# LCL_12V_prec.net
KiCad netlist of a schematic drawn in Altium Designer
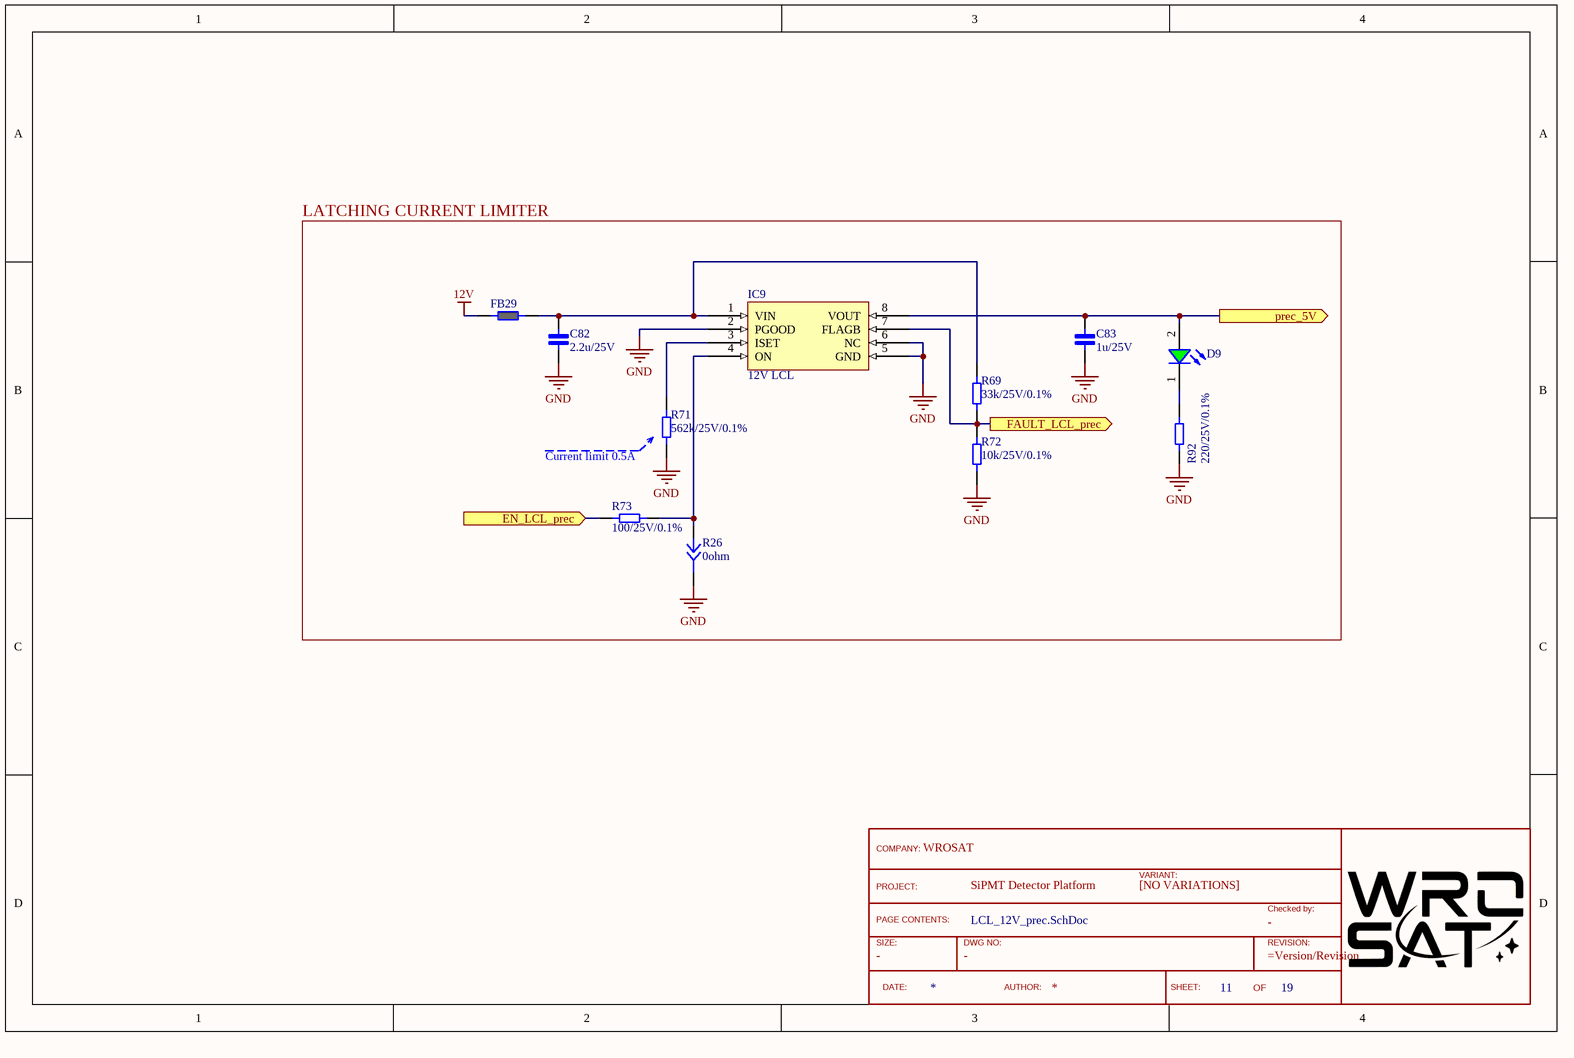
[diagram p0: LCL_12V_prec.SchDoc]

(export (version "E")
  (design (tool "Eeschema 10.0.6"))
  (components
    (comp (ref "C82")
      (value "2.2u/25V")
      (footprint "CAP_0603")
      (description "Ceramic Capacitor 2.2uF / 0603 / 25V / ±5%, Wurth Elektronik MLCC")
      (libsource (lib "Cubesat_lib") (part "Cap_0603_2.2u_25v"))
    )
    (comp (ref "C83")
      (value "1u/25V")
      (footprint "CAP_0603")
      (description "Ceramic Capacitor 1uF / 0603 / 25V / ±5%, Wurth Elektronik MLCC")
      (libsource (lib "Cubesat_lib") (part "Cap_0603_1u_25v"))
    )
    (comp (ref "D9")
      (value "Green, 3.2V")
      (footprint "WL-SMCW_0603_H=0.7mm")
      (description "WL-SMCW SMT Mono-color Chip LED Waterclear, size 0603, Green, 3.2V, 140deg")
      (fields (field (name "PART NUMBER") "150060GS75000") (field (name "PUBLISHER") "Wurth Elektronik"))
      (libsource (lib "LEDS") (part "150060GS75000"))
    )
    (comp (ref "FB29")
      (value "Ferrite_bead_0603")
      (footprint "Ferrite_0603")
      (description "Ferrite bead")
      (libsource (lib "Cubesat_lib") (part "Ferrite_bead_0603"))
    )
    (comp (ref "IC9")
      (value "12V LCL")
      (footprint "SO8")
      (description "FPF270xMX")
      (libsource (lib "Cubesat_lib") (part "FPF2700"))
    )
    (comp (ref "R26")
      (value "0ohm")
      (footprint "Jumper 2")
      (libsource (lib "Cubesat_lib") (part "Mini jumper"))
    )
    (comp (ref "R69")
      (value "33k/25V/0.1%")
      (footprint "RES_0402")
      (description "Vishay, thin film resistor 33k/25V/0.1%")
      (libsource (lib "Cubesat_lib") (part "Res_0402_33k"))
    )
    (comp (ref "R71")
      (value "562k/25V/0.1%")
      (footprint "RES_0402")
      (description "Vishay, thin film resistor 562k/25V/0.1%")
      (libsource (lib "Cubesat_lib") (part "Res_0402_562k"))
    )
    (comp (ref "R72")
      (value "10k/25V/0.1%")
      (footprint "RES_0402")
      (description "Vishay, thin film resistor 10k/25V/0.1%")
      (libsource (lib "Cubesat_lib") (part "Res_0402_10k"))
    )
    (comp (ref "R73")
      (value "100/25V/0.1%")
      (footprint "RES_0402")
      (description "Vishay, thin film resistor 100/25V/0.1%")
      (libsource (lib "Cubesat_lib") (part "Res_0402_100"))
    )
    (comp (ref "R92")
      (value "220/25V/0.1%")
      (footprint "RES_0402")
      (description "Vishay, thin film resistor 1/25V/0.1%")
      (libsource (lib "Cubesat_lib") (part "Res_0402_1"))
    )
  )
  (nets
    (net (code "1") (name "/EN_LCL_prec") (class "Default")
      (node (ref "R73") (pin "1") (pinfunction "1_1") (pintype "passive"))
    )
    (net (code "2") (name "/FAULT_LCL_prec") (class "Default")
      (node (ref "IC9") (pin "7") (pinfunction "FLAGB_7") (pintype "input"))
      (node (ref "R69") (pin "1") (pinfunction "1_1") (pintype "passive"))
      (node (ref "R72") (pin "2") (pinfunction "2_2") (pintype "passive"))
    )
    (net (code "3") (name "/prec_5V") (class "Default")
      (node (ref "C83") (pin "2") (pinfunction "2_2") (pintype "passive"))
      (node (ref "D9") (pin "2") (pinfunction "A_2") (pintype "passive"))
      (node (ref "IC9") (pin "8") (pinfunction "VOUT_8") (pintype "input"))
    )
    (net (code "4") (name "12V") (class "Default")
      (node (ref "FB29") (pin "1") (pinfunction "1_1") (pintype "passive"))
    )
    (net (code "5") (name "GND") (class "Default")
      (node (ref "C82") (pin "1") (pinfunction "1_1") (pintype "passive"))
      (node (ref "C83") (pin "1") (pinfunction "1_1") (pintype "passive"))
      (node (ref "IC9") (pin "2") (pinfunction "PGOOD_2") (pintype "input"))
      (node (ref "IC9") (pin "5") (pinfunction "GND_5") (pintype "input"))
      (node (ref "IC9") (pin "6") (pinfunction "NC_6") (pintype "input"))
      (node (ref "R26") (pin "2") (pinfunction "2_2") (pintype "passive"))
      (node (ref "R71") (pin "1") (pinfunction "1_1") (pintype "passive"))
      (node (ref "R72") (pin "1") (pinfunction "1_1") (pintype "passive"))
      (node (ref "R92") (pin "1") (pinfunction "1_1") (pintype "passive"))
    )
    (net (code "6") (name "Net-(D9-K)") (class "Default")
      (node (ref "D9") (pin "1") (pinfunction "K_1") (pintype "passive"))
      (node (ref "R92") (pin "2") (pinfunction "2_2") (pintype "passive"))
    )
    (net (code "7") (name "Net-(IC9-ISET)") (class "Default")
      (node (ref "IC9") (pin "3") (pinfunction "ISET_3") (pintype "input"))
      (node (ref "R71") (pin "2") (pinfunction "2_2") (pintype "passive"))
    )
    (net (code "8") (name "Net-(IC9-ON)") (class "Default")
      (node (ref "IC9") (pin "4") (pinfunction "ON_4") (pintype "input"))
      (node (ref "R26") (pin "1") (pinfunction "1_1") (pintype "passive"))
      (node (ref "R73") (pin "2") (pinfunction "2_2") (pintype "passive"))
    )
    (net (code "9") (name "Net-(IC9-VIN)") (class "Default")
      (node (ref "C82") (pin "2") (pinfunction "2_2") (pintype "passive"))
      (node (ref "FB29") (pin "2") (pinfunction "2_2") (pintype "passive"))
      (node (ref "IC9") (pin "1") (pinfunction "VIN_1") (pintype "input"))
      (node (ref "R69") (pin "2") (pinfunction "2_2") (pintype "passive"))
    )
  )
)
